# BMS.net
KiCad netlist of a schematic drawn in Altium Designer
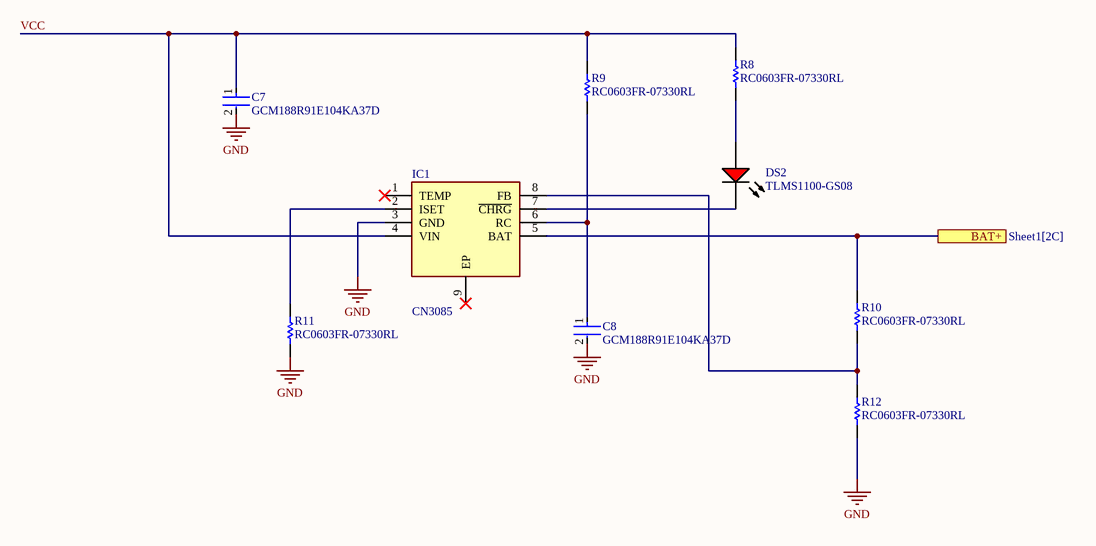
[diagram p0: BMS.SchDoc]

(export (version "E")
  (design (tool "Eeschema 10.0.6"))
  (components
    (comp (ref "C7")
      (value "GCM188R91E104KA37D")
      (footprint "FP-GCM188-0_1-IPC_A")
      (description "Ceramic Capacitor for Automotive 100nF  ±10% 25VDC X8R 0603 Paper T/R")
      (fields (field (name "TOLERANCE") "10%"))
      (libsource (lib "Altium Content Vault") (part "02cd4be3c70576c341d710602a673aa"))
    )
    (comp (ref "C8")
      (value "GCM188R91E104KA37D")
      (footprint "FP-GCM188-0_1-IPC_A")
      (description "Ceramic Capacitor for Automotive 100nF  ±10% 25VDC X8R 0603 Paper T/R")
      (fields (field (name "TOLERANCE") "10%"))
      (libsource (lib "Altium Content Vault") (part "02cd4be3c70576c341d710602a673aa"))
    )
    (comp (ref "DS2")
      (value "TLMS1100-GS08")
      (footprint "VISH-TLMX1100_V")
      (description "LED, RED, 2.1 V, -40 to 100 degC, 2-Pin SMD (0603), RoHS, Tape and Reel")
      (fields (field (name "TOLERANCE") "5%"))
      (libsource (lib "Altium Content Vault") (part "LED-RED-AK-2"))
    )
    (comp (ref "IC1")
      (value "CN3085")
      (footprint "SamacSys:SOIC127P600X175-9N")
      (description "Integrated Circuit")
      (libsource (lib "*") (part "CN3085"))
    )
    (comp (ref "R8")
      (value "RC0603FR-07330RL")
      (footprint "RESC1608X55X25ML10T15")
      (description "Chip Resistor, 330 Ohm, +/- 1%, 0.1 W, -55 to 155 degC, 0603 (1608 Metric), RoHS, Tape and Reel")
      (fields (field (name "TOLERANCE") "10%"))
      (libsource (lib "Altium Content Vault") (part "RES-2"))
    )
    (comp (ref "R9")
      (value "RC0603FR-07330RL")
      (footprint "RESC1608X55X25ML10T15")
      (description "Chip Resistor, 330 Ohm, +/- 1%, 0.1 W, -55 to 155 degC, 0603 (1608 Metric), RoHS, Tape and Reel")
      (fields (field (name "TOLERANCE") "10%"))
      (libsource (lib "Altium Content Vault") (part "RES-2"))
    )
    (comp (ref "R10")
      (value "RC0603FR-07330RL")
      (footprint "RESC1608X55X25ML10T15")
      (description "Chip Resistor, 330 Ohm, +/- 1%, 0.1 W, -55 to 155 degC, 0603 (1608 Metric), RoHS, Tape and Reel")
      (fields (field (name "TOLERANCE") "10%"))
      (libsource (lib "Altium Content Vault") (part "RES-2"))
    )
    (comp (ref "R11")
      (value "RC0603FR-07330RL")
      (footprint "RESC1608X55X25ML10T15")
      (description "Chip Resistor, 330 Ohm, +/- 1%, 0.1 W, -55 to 155 degC, 0603 (1608 Metric), RoHS, Tape and Reel")
      (fields (field (name "TOLERANCE") "10%"))
      (libsource (lib "Altium Content Vault") (part "RES-2"))
    )
    (comp (ref "R12")
      (value "RC0603FR-07330RL")
      (footprint "RESC1608X55X25ML10T15")
      (description "Chip Resistor, 330 Ohm, +/- 1%, 0.1 W, -55 to 155 degC, 0603 (1608 Metric), RoHS, Tape and Reel")
      (fields (field (name "TOLERANCE") "10%"))
      (libsource (lib "Altium Content Vault") (part "RES-2"))
    )
  )
  (nets
    (net (code "1") (name "/BAT+") (class "Default")
      (node (ref "IC1") (pin "5") (pinfunction "BAT_5") (pintype "passive"))
      (node (ref "R10") (pin "1") (pinfunction "1_1") (pintype "passive"))
    )
    (net (code "2") (name "/VCC") (class "Default")
      (node (ref "C7") (pin "1") (pinfunction "1_1") (pintype "passive"))
      (node (ref "IC1") (pin "4") (pinfunction "VIN_4") (pintype "passive"))
      (node (ref "R8") (pin "1") (pinfunction "1_1") (pintype "passive"))
      (node (ref "R9") (pin "1") (pinfunction "1_1") (pintype "passive"))
    )
    (net (code "3") (name "GND") (class "Default")
      (node (ref "C7") (pin "2") (pinfunction "2_2") (pintype "passive"))
      (node (ref "C8") (pin "2") (pinfunction "2_2") (pintype "passive"))
      (node (ref "IC1") (pin "3") (pinfunction "GND_3") (pintype "passive"))
      (node (ref "R11") (pin "2") (pinfunction "2_2") (pintype "passive"))
      (node (ref "R12") (pin "2") (pinfunction "2_2") (pintype "passive"))
    )
    (net (code "4") (name "Net-(DS2-A)") (class "Default")
      (node (ref "DS2") (pin "1") (pinfunction "A_1") (pintype "passive"))
      (node (ref "R8") (pin "2") (pinfunction "2_2") (pintype "passive"))
    )
    (net (code "5") (name "Net-(DS2-K)") (class "Default")
      (node (ref "DS2") (pin "2") (pinfunction "K_2") (pintype "passive"))
      (node (ref "IC1") (pin "7") (pinfunction "~{CHRG}_7") (pintype "passive"))
    )
    (net (code "6") (name "Net-(IC1-FB)") (class "Default")
      (node (ref "IC1") (pin "8") (pinfunction "FB_8") (pintype "passive"))
      (node (ref "R10") (pin "2") (pinfunction "2_2") (pintype "passive"))
      (node (ref "R12") (pin "1") (pinfunction "1_1") (pintype "passive"))
    )
    (net (code "7") (name "Net-(IC1-ISET)") (class "Default")
      (node (ref "IC1") (pin "2") (pinfunction "ISET_2") (pintype "passive"))
      (node (ref "R11") (pin "1") (pinfunction "1_1") (pintype "passive"))
    )
    (net (code "8") (name "Net-(IC1-RC)") (class "Default")
      (node (ref "C8") (pin "1") (pinfunction "1_1") (pintype "passive"))
      (node (ref "IC1") (pin "6") (pinfunction "RC_6") (pintype "passive"))
      (node (ref "R9") (pin "2") (pinfunction "2_2") (pintype "passive"))
    )
    (net (code "9") (name "unconnected-(IC1-EP-Pad9)") (class "Default")
      (node (ref "IC1") (pin "9") (pinfunction "EP_9") (pintype "passive+no_connect"))
    )
    (net (code "10") (name "unconnected-(IC1-TEMP-Pad1)") (class "Default")
      (node (ref "IC1") (pin "1") (pinfunction "TEMP_1") (pintype "passive+no_connect"))
    )
  )
)
